# I2C_AccGyro.net
KiCad netlist of a schematic drawn in Altium Designer
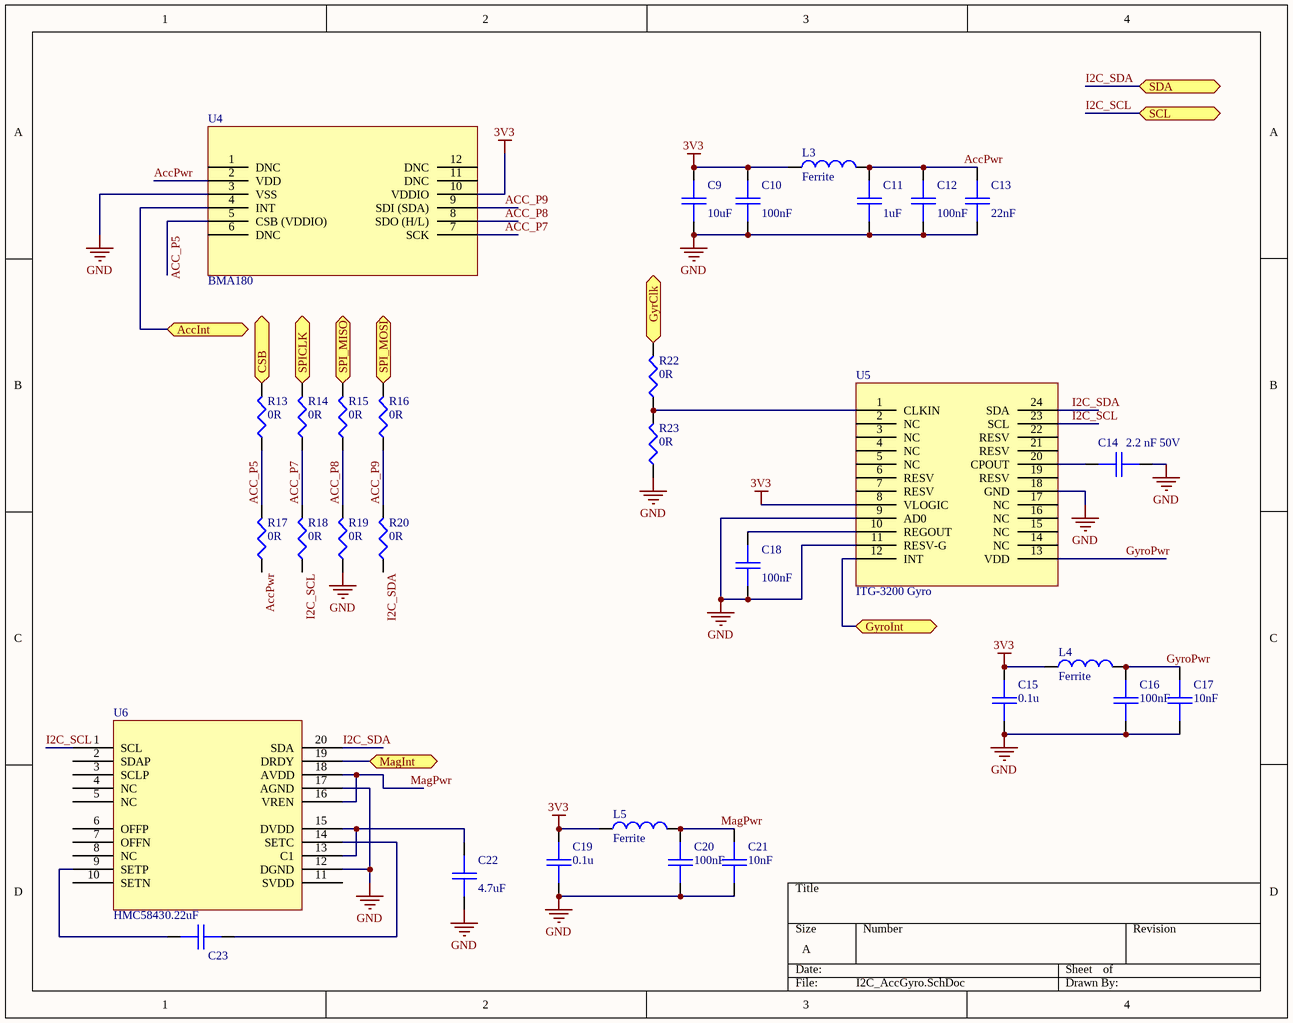
[diagram p0: I2C_AccGyro.SchDoc]

(export (version "E")
  (design (tool "Eeschema 10.0.6"))
  (components
    (comp (ref "C9")
      (value "10uF")
      (footprint "0603")
      (description "Capacitor")
      (fields (field (name "Comment") "10u"))
      (libsource (lib "RCLDQ") (part "CAP"))
    )
    (comp (ref "C10")
      (value "100nF")
      (footprint "0603")
      (description "Capacitor")
      (fields (field (name "Comment") "0.1u"))
      (libsource (lib "RCLDQ") (part "CAP"))
    )
    (comp (ref "C11")
      (value "1uF")
      (footprint "0603")
      (description "Capacitor")
      (fields (field (name "Comment") "1u"))
      (libsource (lib "RCLDQ") (part "CAP"))
    )
    (comp (ref "C12")
      (value "100nF")
      (footprint "0603")
      (description "Capacitor")
      (libsource (lib "RCLDQ") (part "CAP"))
    )
    (comp (ref "C13")
      (value "22nF")
      (footprint "0603")
      (description "Capacitor")
      (libsource (lib "RCLDQ") (part "CAP"))
    )
    (comp (ref "C14")
      (value "2.2 nF 50V")
      (footprint "0603")
      (description "Capacitor")
      (fields (field (name "Comment") "2.2n 50V"))
      (libsource (lib "2009_BatteryMaster") (part "CAP"))
    )
    (comp (ref "C15")
      (value "0.1u")
      (footprint "0603")
      (description "Capacitor")
      (libsource (lib "RCLDQ") (part "CAP"))
    )
    (comp (ref "C16")
      (value "100nF")
      (footprint "0603")
      (description "Capacitor")
      (libsource (lib "RCLDQ") (part "CAP"))
    )
    (comp (ref "C17")
      (value "10nF")
      (footprint "0603")
      (description "Capacitor")
      (libsource (lib "RCLDQ") (part "CAP"))
    )
    (comp (ref "C18")
      (value "100nF")
      (footprint "0603")
      (description "Capacitor")
      (fields (field (name "Comment") "100n"))
      (libsource (lib "2009_BatteryMaster") (part "CAP"))
    )
    (comp (ref "C19")
      (value "0.1u")
      (footprint "0603")
      (description "Capacitor")
      (libsource (lib "RCLDQ") (part "CAP"))
    )
    (comp (ref "C20")
      (value "100nF")
      (footprint "0603")
      (description "Capacitor")
      (libsource (lib "RCLDQ") (part "CAP"))
    )
    (comp (ref "C21")
      (value "10nF")
      (footprint "0603")
      (description "Capacitor")
      (libsource (lib "RCLDQ") (part "CAP"))
    )
    (comp (ref "C22")
      (value "4.7uF")
      (footprint "0603")
      (description "Capacitor")
      (fields (field (name "Comment") "4.7u"))
      (libsource (lib "RCLDQ") (part "CAP"))
    )
    (comp (ref "C23")
      (value "0.22uF")
      (footprint "0603")
      (description "Capacitor")
      (fields (field (name "Comment") "0.22u"))
      (libsource (lib "RCLDQ") (part "CAP"))
    )
    (comp (ref "L3")
      (value "Ferrite")
      (footprint "0603")
      (description "Inductor")
      (fields (field (name "MANUFACTURER") "Generic Components") (field (name "PUBLISHER") "Altium Limited"))
      (libsource (lib "RCLDQ") (part "INDUCTOR"))
    )
    (comp (ref "L4")
      (value "Ferrite")
      (footprint "0603")
      (description "Inductor")
      (fields (field (name "MANUFACTURER") "Generic Components") (field (name "PUBLISHER") "Altium Limited"))
      (libsource (lib "RCLDQ") (part "INDUCTOR"))
    )
    (comp (ref "L5")
      (value "Ferrite")
      (footprint "0603")
      (description "Inductor")
      (fields (field (name "MANUFACTURER") "Generic Components") (field (name "PUBLISHER") "Altium Limited"))
      (libsource (lib "RCLDQ") (part "INDUCTOR"))
    )
    (comp (ref "R13")
      (value "0R")
      (footprint "0603")
      (description "Resistor")
      (libsource (lib "2009_BatteryMaster") (part "RES1"))
    )
    (comp (ref "R14")
      (value "0R")
      (footprint "0603")
      (description "Resistor")
      (libsource (lib "2009_BatteryMaster") (part "RES1"))
    )
    (comp (ref "R15")
      (value "0R")
      (footprint "0603")
      (description "Resistor")
      (libsource (lib "2009_BatteryMaster") (part "RES1"))
    )
    (comp (ref "R16")
      (value "0R")
      (footprint "0603")
      (description "Resistor")
      (libsource (lib "2009_BatteryMaster") (part "RES1"))
    )
    (comp (ref "R17")
      (value "0R")
      (footprint "0603")
      (description "Resistor")
      (libsource (lib "2009_BatteryMaster") (part "RES1"))
    )
    (comp (ref "R18")
      (value "0R")
      (footprint "0603")
      (description "Resistor")
      (libsource (lib "2009_BatteryMaster") (part "RES1"))
    )
    (comp (ref "R19")
      (value "0R")
      (footprint "0603")
      (description "Resistor")
      (libsource (lib "2009_BatteryMaster") (part "RES1"))
    )
    (comp (ref "R20")
      (value "0R")
      (footprint "0603")
      (description "Resistor")
      (libsource (lib "2009_BatteryMaster") (part "RES1"))
    )
    (comp (ref "R22")
      (value "0R")
      (footprint "0603")
      (description "Resistor")
      (libsource (lib "2009_BatteryMaster") (part "RES1"))
    )
    (comp (ref "R23")
      (value "0R")
      (footprint "0603")
      (description "Resistor")
      (libsource (lib "2009_BatteryMaster") (part "RES1"))
    )
    (comp (ref "U4") (value "BMA180") (footprint "LGA - BMA180") (libsource (lib "TiltLib") (part "BMA180")))
    (comp (ref "U5")
      (value "ITG-3200 Gyro")
      (footprint "ITG-3200 - QFN 24 Pin")
      (libsource (lib "TiltLib") (part "ITG-3200"))
    )
    (comp (ref "U6")
      (value "HMC5843")
      (footprint "HMC5843 - LPCC 20 Pin")
      (libsource (lib "TiltLib") (part "HMC5843"))
    )
  )
  (nets
    (net (code "1") (name "/ACC_P5") (class "Default")
      (node (ref "R13") (pin "1") (pinfunction "1_1") (pintype "passive"))
      (node (ref "R17") (pin "2") (pinfunction "2_2") (pintype "passive"))
      (node (ref "U4") (pin "5") (pinfunction "CSB_(VDDIO)_5") (pintype "passive"))
    )
    (net (code "2") (name "/ACC_P7") (class "Default")
      (node (ref "R14") (pin "1") (pinfunction "1_1") (pintype "passive"))
      (node (ref "R18") (pin "2") (pinfunction "2_2") (pintype "passive"))
      (node (ref "U4") (pin "7") (pinfunction "SCK_7") (pintype "passive"))
    )
    (net (code "3") (name "/ACC_P8") (class "Default")
      (node (ref "R15") (pin "1") (pinfunction "1_1") (pintype "passive"))
      (node (ref "R19") (pin "2") (pinfunction "2_2") (pintype "passive"))
      (node (ref "U4") (pin "8") (pinfunction "SDO_(H/L)_8") (pintype "passive"))
    )
    (net (code "4") (name "/ACC_P9") (class "Default")
      (node (ref "R16") (pin "1") (pinfunction "1_1") (pintype "passive"))
      (node (ref "R20") (pin "2") (pinfunction "2_2") (pintype "passive"))
      (node (ref "U4") (pin "9") (pinfunction "SDI_(SDA)_9") (pintype "passive"))
    )
    (net (code "5") (name "/AccInt") (class "Default")
      (node (ref "U4") (pin "4") (pinfunction "INT_4") (pintype "passive"))
    )
    (net (code "6") (name "/AccPwr") (class "Default")
      (node (ref "C11") (pin "1") (pinfunction "1_1") (pintype "passive"))
      (node (ref "C12") (pin "1") (pinfunction "1_1") (pintype "passive"))
      (node (ref "C13") (pin "1") (pinfunction "1_1") (pintype "passive"))
      (node (ref "L3") (pin "2") (pinfunction "2_2") (pintype "passive"))
      (node (ref "R17") (pin "1") (pinfunction "1_1") (pintype "passive"))
      (node (ref "U4") (pin "2") (pinfunction "VDD_2") (pintype "passive"))
    )
    (net (code "7") (name "/CSB") (class "Default")
      (node (ref "R13") (pin "2") (pinfunction "2_2") (pintype "passive"))
    )
    (net (code "8") (name "/GyrClk") (class "Default")
      (node (ref "R22") (pin "2") (pinfunction "2_2") (pintype "passive"))
    )
    (net (code "9") (name "/GyroInt") (class "Default")
      (node (ref "U5") (pin "12") (pinfunction "INT_12") (pintype "passive"))
    )
    (net (code "10") (name "/GyroPwr") (class "Default")
      (node (ref "C16") (pin "1") (pinfunction "1_1") (pintype "passive"))
      (node (ref "C17") (pin "1") (pinfunction "1_1") (pintype "passive"))
      (node (ref "L4") (pin "2") (pinfunction "2_2") (pintype "passive"))
      (node (ref "U5") (pin "13") (pinfunction "VDD_13") (pintype "passive"))
    )
    (net (code "11") (name "/I2C_SCL") (class "Default")
      (node (ref "R18") (pin "1") (pinfunction "1_1") (pintype "passive"))
      (node (ref "U5") (pin "23") (pinfunction "SCL_23") (pintype "passive"))
      (node (ref "U6") (pin "1") (pinfunction "SCL_1") (pintype "passive"))
    )
    (net (code "12") (name "/I2C_SDA") (class "Default")
      (node (ref "R20") (pin "1") (pinfunction "1_1") (pintype "passive"))
      (node (ref "U5") (pin "24") (pinfunction "SDA_24") (pintype "passive"))
      (node (ref "U6") (pin "20") (pinfunction "SDA_20") (pintype "passive"))
    )
    (net (code "13") (name "/MagInt") (class "Default")
      (node (ref "U6") (pin "19") (pinfunction "DRDY_19") (pintype "passive"))
    )
    (net (code "14") (name "/MagPwr") (class "Default")
      (node (ref "C20") (pin "1") (pinfunction "1_1") (pintype "passive"))
      (node (ref "C21") (pin "1") (pinfunction "1_1") (pintype "passive"))
      (node (ref "L5") (pin "2") (pinfunction "2_2") (pintype "passive"))
      (node (ref "U6") (pin "16") (pinfunction "VREN_16") (pintype "passive"))
      (node (ref "U6") (pin "18") (pinfunction "AVDD_18") (pintype "passive"))
    )
    (net (code "15") (name "/SPICLK") (class "Default")
      (node (ref "R14") (pin "2") (pinfunction "2_2") (pintype "passive"))
    )
    (net (code "16") (name "/SPI_MISO") (class "Default")
      (node (ref "R15") (pin "2") (pinfunction "2_2") (pintype "passive"))
    )
    (net (code "17") (name "/SPI_MOSI") (class "Default")
      (node (ref "R16") (pin "2") (pinfunction "2_2") (pintype "passive"))
    )
    (net (code "18") (name "3V3") (class "Default")
      (node (ref "C10") (pin "1") (pinfunction "1_1") (pintype "passive"))
      (node (ref "C15") (pin "1") (pinfunction "1_1") (pintype "passive"))
      (node (ref "C19") (pin "1") (pinfunction "1_1") (pintype "passive"))
      (node (ref "C9") (pin "1") (pinfunction "1_1") (pintype "passive"))
      (node (ref "L3") (pin "1") (pinfunction "1_1") (pintype "passive"))
      (node (ref "L4") (pin "1") (pinfunction "1_1") (pintype "passive"))
      (node (ref "L5") (pin "1") (pinfunction "1_1") (pintype "passive"))
      (node (ref "U4") (pin "10") (pinfunction "VDDIO_10") (pintype "passive"))
      (node (ref "U5") (pin "8") (pinfunction "VLOGIC_8") (pintype "passive"))
    )
    (net (code "19") (name "GND") (class "Default")
      (node (ref "C10") (pin "2") (pinfunction "2_2") (pintype "passive"))
      (node (ref "C11") (pin "2") (pinfunction "2_2") (pintype "passive"))
      (node (ref "C12") (pin "2") (pinfunction "2_2") (pintype "passive"))
      (node (ref "C13") (pin "2") (pinfunction "2_2") (pintype "passive"))
      (node (ref "C14") (pin "2") (pinfunction "2_2") (pintype "passive"))
      (node (ref "C15") (pin "2") (pinfunction "2_2") (pintype "passive"))
      (node (ref "C16") (pin "2") (pinfunction "2_2") (pintype "passive"))
      (node (ref "C17") (pin "2") (pinfunction "2_2") (pintype "passive"))
      (node (ref "C18") (pin "2") (pinfunction "2_2") (pintype "passive"))
      (node (ref "C19") (pin "2") (pinfunction "2_2") (pintype "passive"))
      (node (ref "C20") (pin "2") (pinfunction "2_2") (pintype "passive"))
      (node (ref "C21") (pin "2") (pinfunction "2_2") (pintype "passive"))
      (node (ref "C22") (pin "2") (pinfunction "2_2") (pintype "passive"))
      (node (ref "C9") (pin "2") (pinfunction "2_2") (pintype "passive"))
      (node (ref "R19") (pin "1") (pinfunction "1_1") (pintype "passive"))
      (node (ref "R23") (pin "1") (pinfunction "1_1") (pintype "passive"))
      (node (ref "U4") (pin "3") (pinfunction "VSS_3") (pintype "passive"))
      (node (ref "U5") (pin "11") (pinfunction "RESV-G_11") (pintype "passive"))
      (node (ref "U5") (pin "18") (pinfunction "GND_18") (pintype "passive"))
      (node (ref "U5") (pin "9") (pinfunction "AD0_9") (pintype "passive"))
      (node (ref "U6") (pin "12") (pinfunction "DGND_12") (pintype "passive"))
      (node (ref "U6") (pin "17") (pinfunction "AGND_17") (pintype "passive"))
    )
    (net (code "20") (name "Net-(U5-CLKIN)") (class "Default")
      (node (ref "R22") (pin "1") (pinfunction "1_1") (pintype "passive"))
      (node (ref "R23") (pin "2") (pinfunction "2_2") (pintype "passive"))
      (node (ref "U5") (pin "1") (pinfunction "CLKIN_1") (pintype "passive"))
    )
    (net (code "21") (name "Net-(U5-CPOUT)") (class "Default")
      (node (ref "C14") (pin "1") (pinfunction "1_1") (pintype "passive"))
      (node (ref "U5") (pin "20") (pinfunction "CPOUT_20") (pintype "passive"))
    )
    (net (code "22") (name "Net-(U5-REGOUT)") (class "Default")
      (node (ref "C18") (pin "1") (pinfunction "1_1") (pintype "passive"))
      (node (ref "U5") (pin "10") (pinfunction "REGOUT_10") (pintype "passive"))
    )
    (net (code "23") (name "Net-(U6-C1)") (class "Default")
      (node (ref "C22") (pin "1") (pinfunction "1_1") (pintype "passive"))
      (node (ref "U6") (pin "13") (pinfunction "C1_13") (pintype "passive"))
      (node (ref "U6") (pin "15") (pinfunction "DVDD_15") (pintype "passive"))
    )
    (net (code "24") (name "Net-(U6-SETC)") (class "Default")
      (node (ref "C23") (pin "1") (pinfunction "1_1") (pintype "passive"))
      (node (ref "U6") (pin "14") (pinfunction "SETC_14") (pintype "passive"))
    )
    (net (code "25") (name "Net-(U6-SETP)") (class "Default")
      (node (ref "C23") (pin "2") (pinfunction "2_2") (pintype "passive"))
      (node (ref "U6") (pin "9") (pinfunction "SETP_9") (pintype "passive"))
    )
    (net (code "26") (name "unconnected-(U4-DNC-Pad1)") (class "Default")
      (node (ref "U4") (pin "1") (pinfunction "DNC_1") (pintype "passive"))
    )
    (net (code "27") (name "unconnected-(U4-DNC-Pad6)") (class "Default")
      (node (ref "U4") (pin "6") (pinfunction "DNC_6") (pintype "passive"))
    )
    (net (code "28") (name "unconnected-(U4-DNC-Pad11)") (class "Default")
      (node (ref "U4") (pin "11") (pinfunction "DNC_11") (pintype "passive"))
    )
    (net (code "29") (name "unconnected-(U4-DNC-Pad12)") (class "Default")
      (node (ref "U4") (pin "12") (pinfunction "DNC_12") (pintype "passive"))
    )
    (net (code "30") (name "unconnected-(U5-NC-Pad2)") (class "Default")
      (node (ref "U5") (pin "2") (pinfunction "NC_2") (pintype "passive"))
    )
    (net (code "31") (name "unconnected-(U5-NC-Pad3)") (class "Default")
      (node (ref "U5") (pin "3") (pinfunction "NC_3") (pintype "passive"))
    )
    (net (code "32") (name "unconnected-(U5-NC-Pad4)") (class "Default")
      (node (ref "U5") (pin "4") (pinfunction "NC_4") (pintype "passive"))
    )
    (net (code "33") (name "unconnected-(U5-NC-Pad5)") (class "Default")
      (node (ref "U5") (pin "5") (pinfunction "NC_5") (pintype "passive"))
    )
    (net (code "34") (name "unconnected-(U5-NC-Pad14)") (class "Default")
      (node (ref "U5") (pin "14") (pinfunction "NC_14") (pintype "passive"))
    )
    (net (code "35") (name "unconnected-(U5-NC-Pad15)") (class "Default")
      (node (ref "U5") (pin "15") (pinfunction "NC_15") (pintype "passive"))
    )
    (net (code "36") (name "unconnected-(U5-NC-Pad16)") (class "Default")
      (node (ref "U5") (pin "16") (pinfunction "NC_16") (pintype "passive"))
    )
    (net (code "37") (name "unconnected-(U5-NC-Pad17)") (class "Default")
      (node (ref "U5") (pin "17") (pinfunction "NC_17") (pintype "passive"))
    )
    (net (code "38") (name "unconnected-(U5-RESV-Pad6)") (class "Default")
      (node (ref "U5") (pin "6") (pinfunction "RESV_6") (pintype "passive"))
    )
    (net (code "39") (name "unconnected-(U5-RESV-Pad7)") (class "Default")
      (node (ref "U5") (pin "7") (pinfunction "RESV_7") (pintype "passive"))
    )
    (net (code "40") (name "unconnected-(U5-RESV-Pad19)") (class "Default")
      (node (ref "U5") (pin "19") (pinfunction "RESV_19") (pintype "passive"))
    )
    (net (code "41") (name "unconnected-(U5-RESV-Pad21)") (class "Default")
      (node (ref "U5") (pin "21") (pinfunction "RESV_21") (pintype "passive"))
    )
    (net (code "42") (name "unconnected-(U5-RESV-Pad22)") (class "Default")
      (node (ref "U5") (pin "22") (pinfunction "RESV_22") (pintype "passive"))
    )
    (net (code "43") (name "unconnected-(U6-NC-Pad4)") (class "Default")
      (node (ref "U6") (pin "4") (pinfunction "NC_4") (pintype "passive"))
    )
    (net (code "44") (name "unconnected-(U6-NC-Pad5)") (class "Default")
      (node (ref "U6") (pin "5") (pinfunction "NC_5") (pintype "passive"))
    )
    (net (code "45") (name "unconnected-(U6-NC-Pad8)") (class "Default")
      (node (ref "U6") (pin "8") (pinfunction "NC_8") (pintype "passive"))
    )
    (net (code "46") (name "unconnected-(U6-OFFN-Pad7)") (class "Default")
      (node (ref "U6") (pin "7") (pinfunction "OFFN_7") (pintype "passive"))
    )
    (net (code "47") (name "unconnected-(U6-OFFP-Pad6)") (class "Default")
      (node (ref "U6") (pin "6") (pinfunction "OFFP_6") (pintype "passive"))
    )
    (net (code "48") (name "unconnected-(U6-SCLP-Pad3)") (class "Default")
      (node (ref "U6") (pin "3") (pinfunction "SCLP_3") (pintype "passive"))
    )
    (net (code "49") (name "unconnected-(U6-SDAP-Pad2)") (class "Default")
      (node (ref "U6") (pin "2") (pinfunction "SDAP_2") (pintype "passive"))
    )
    (net (code "50") (name "unconnected-(U6-SETN-Pad10)") (class "Default")
      (node (ref "U6") (pin "10") (pinfunction "SETN_10") (pintype "passive"))
    )
    (net (code "51") (name "unconnected-(U6-SVDD-Pad11)") (class "Default")
      (node (ref "U6") (pin "11") (pinfunction "SVDD_11") (pintype "passive"))
    )
  )
)
